# ResetCircuit.net
KiCad netlist of a schematic drawn in Altium Designer
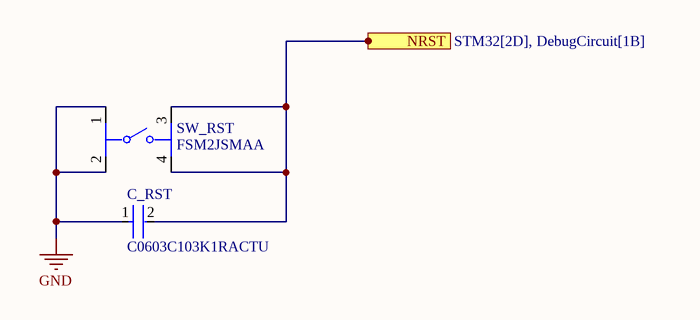
[diagram p0: ResetCircuit.SchDoc]

(export (version "E")
  (design (tool "Eeschema 10.0.6"))
  (components
    (comp (ref "C_RST")
      (value "C0603C103K1RACTU")
      (footprint "FP-C0603C-CF-MFG")
      (description "CAP CER 10000PF 100V X7R 0603")
      (fields
        (field (name "MANUFACTURER") "KEMET")
        (field (name "OCTOPART") "https://octopart.com/c0603c103k1ractu-kemet-134140")
      )
      (libsource (lib "Altium Content Vault") (part "b4654b650e69147ec39a6b967a45e02"))
    )
    (comp (ref "SW_RST")
      (value "FSM2JSMAA")
      (footprint "FP-FSM2JSMAA-MFG")
      (description "SWITCH TACTILE SPST-NO 0.05A 24V")
      (fields
        (field (name "MANUFACTURER") "TE Connectivity")
        (field (name "OCTOPART") "https://octopart.com/fsm2jsmaa-te+connectivity-41720620")
      )
      (libsource (lib "Altium Content Vault") (part "b8895f3f4cefb76e1819d2863dba89b"))
    )
  )
  (nets
    (net (code "1") (name "/NRST") (class "Default")
      (node (ref "C_RST") (pin "2") (pinfunction "2_2") (pintype "passive"))
      (node (ref "SW_RST") (pin "3") (pinfunction "3_3") (pintype "passive"))
      (node (ref "SW_RST") (pin "4") (pinfunction "4_4") (pintype "passive"))
    )
    (net (code "2") (name "GND") (class "Default")
      (node (ref "C_RST") (pin "1") (pinfunction "1_1") (pintype "passive"))
      (node (ref "SW_RST") (pin "1") (pinfunction "1_1") (pintype "passive"))
      (node (ref "SW_RST") (pin "2") (pinfunction "2_2") (pintype "passive"))
    )
  )
)
